# board-v2.net
KiCad netlist of a schematic drawn in EAGLE
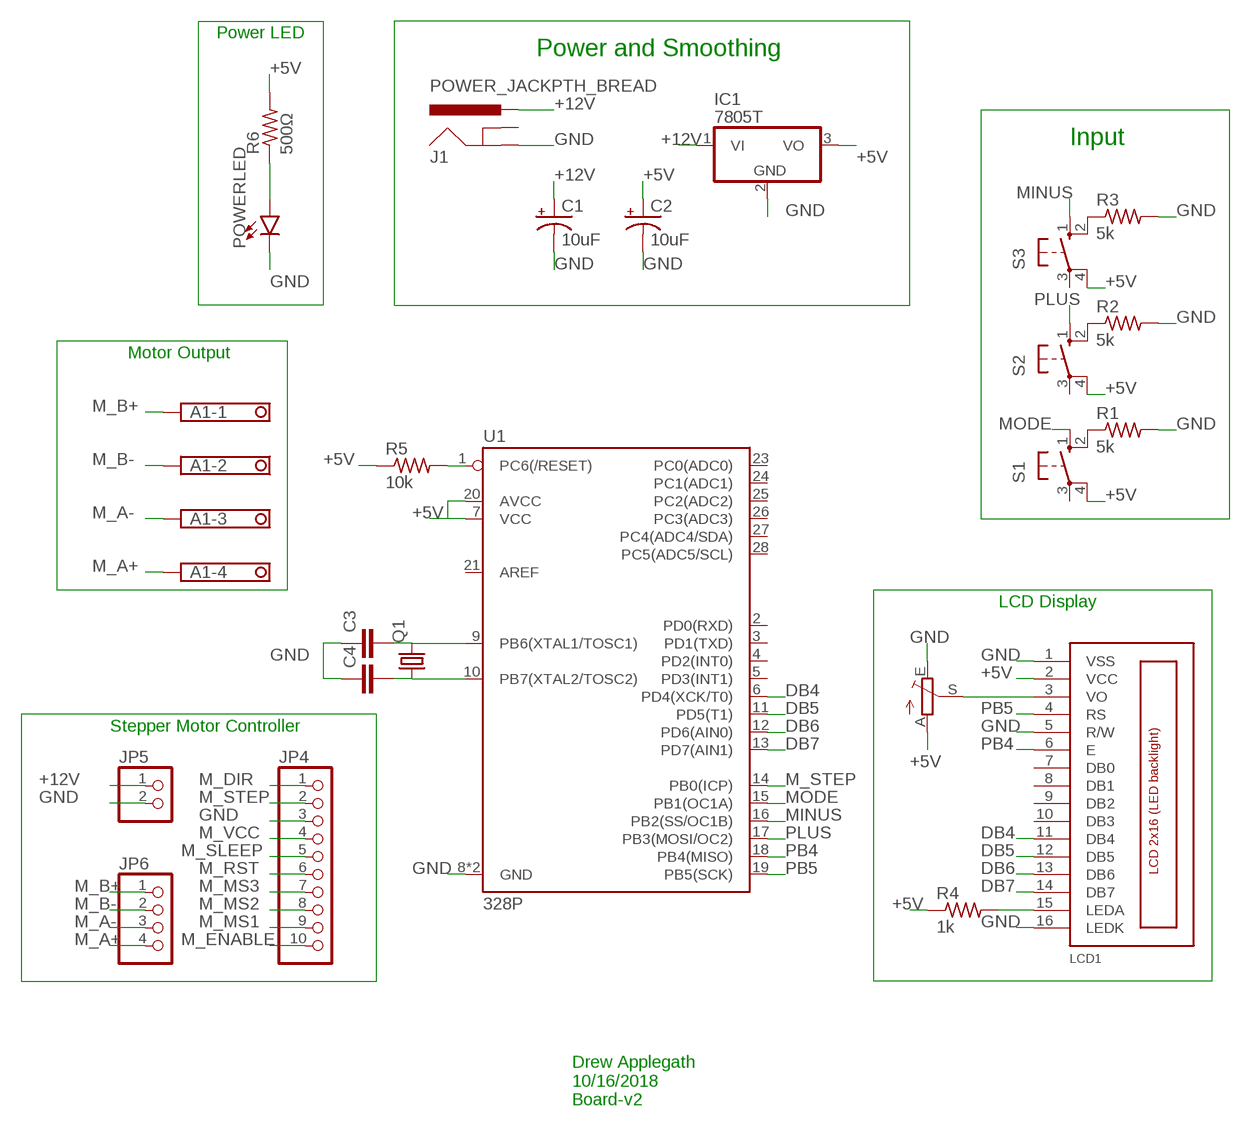
[diagram p0: schematic, sheet 1]

(export (version "E")
  (design (tool "Eeschema 10.0.6"))
  (components
    (comp (ref "A1")
      (value "TERMINAL-BLOCK-3.5MM-4-PIN-LONG-PAD")
      (footprint "eagle-import:TERMINAL-BLOCK-4-PIN-3.5MM-LONG-PAD")
      (libsource (lib "eagle-import") (part "TERMINAL-BLOCK-3.5MM-4-PIN-LONG-PAD"))
    )
    (comp (ref "C1")
      (value "10uF")
      (footprint "eagle-import:CPOL-RADIAL-2.5MM-5MM")
      (libsource (lib "eagle-import") (part "10UF-POLAR-RADIAL-2.5MM-25V-20%"))
    )
    (comp (ref "C2")
      (value "10uF")
      (footprint "eagle-import:CPOL-RADIAL-2.5MM-5MM")
      (libsource (lib "eagle-import") (part "10UF-POLAR-RADIAL-2.5MM-25V-20%"))
    )
    (comp (ref "C3")
      (value "C-EU025-024X044")
      (footprint "eagle-import:C025-024X044")
      (libsource (lib "eagle-import") (part "C-EU025-024X044"))
    )
    (comp (ref "C4")
      (value "C-EU025-024X044")
      (footprint "eagle-import:C025-024X044")
      (libsource (lib "eagle-import") (part "C-EU025-024X044"))
    )
    (comp (ref "IC1")
      (value "7805T")
      (footprint "eagle-import:TO220H")
      (libsource (lib "eagle-import") (part "78T05"))
    )
    (comp (ref "J1")
      (value "POWER_JACKPTH_BREAD")
      (footprint "eagle-import:POWER_JACK_PTH_BREAD")
      (libsource (lib "eagle-import") (part "POWER_JACKPTH_BREAD"))
    )
    (comp (ref "JP4")
      (value "PINHD-1X10")
      (footprint "eagle-import:1X10")
      (libsource (lib "eagle-import") (part "PINHD-1X10"))
    )
    (comp (ref "JP5")
      (value "PINHD-1X2")
      (footprint "eagle-import:1X02")
      (libsource (lib "eagle-import") (part "PINHD-1X2"))
    )
    (comp (ref "JP6")
      (value "PINHD-1X4")
      (footprint "eagle-import:1X04")
      (libsource (lib "eagle-import") (part "PINHD-1X4"))
    )
    (comp (ref "LCD1")
      (value "LCD_2X16_SIL")
      (footprint "eagle-import:HY-1602F")
      (libsource (lib "eagle-import") (part "LCD_2X16_SIL"))
    )
    (comp (ref "POWERLED")
      (value "LED-3MM-NO_SILK")
      (footprint "eagle-import:LED_3MM-NS")
      (libsource (lib "eagle-import") (part "LED-3MM-NO_SILK"))
    )
    (comp (ref "Q1")
      (value "CRYSTALHC49S")
      (footprint "eagle-import:HC49_S")
      (libsource (lib "eagle-import") (part "CRYSTALHC49S"))
    )
    (comp (ref "R1")
      (value "5k")
      (footprint "eagle-import:0207_7")
      (libsource (lib "eagle-import") (part "R-US_0207/7"))
    )
    (comp (ref "R2")
      (value "5k")
      (footprint "eagle-import:0207_7")
      (libsource (lib "eagle-import") (part "R-US_0207/7"))
    )
    (comp (ref "R3")
      (value "5k")
      (footprint "eagle-import:0207_7")
      (libsource (lib "eagle-import") (part "R-US_0207/7"))
    )
    (comp (ref "R4")
      (value "1k")
      (footprint "eagle-import:0207_7")
      (libsource (lib "eagle-import") (part "R-US_0207/7"))
    )
    (comp (ref "R5")
      (value "10k")
      (footprint "eagle-import:0207_7")
      (libsource (lib "eagle-import") (part "R-US_0207/7"))
    )
    (comp (ref "R6")
      (value "500Ω")
      (footprint "eagle-import:0207_7")
      (libsource (lib "eagle-import") (part "R-US_0207/7"))
    )
    (comp (ref "R7")
      (value "TRIM_EU-S63S")
      (footprint "eagle-import:S63S")
      (libsource (lib "eagle-import") (part "TRIM_EU-S63S"))
    )
    (comp (ref "S1")
      (value "40-XX")
      (footprint "eagle-import:B3F-40XX")
      (fields (field (name "MF") "OMRON COMPONENTS USA") (field (name "MPN") "B3F-4000"))
      (libsource (lib "eagle-import") (part "40-XX"))
    )
    (comp (ref "S2")
      (value "40-XX")
      (footprint "eagle-import:B3F-40XX")
      (fields (field (name "MF") "OMRON COMPONENTS USA") (field (name "MPN") "B3F-4000"))
      (libsource (lib "eagle-import") (part "40-XX"))
    )
    (comp (ref "S3")
      (value "40-XX")
      (footprint "eagle-import:B3F-40XX")
      (fields (field (name "MF") "OMRON COMPONENTS USA") (field (name "MPN") "B3F-4000"))
      (libsource (lib "eagle-import") (part "40-XX"))
    )
    (comp (ref "U1")
      (value "328P")
      (footprint "eagle-import:DIP28")
      (libsource (lib "eagle-import") (part "ATMEGA328P_PDIP"))
    )
  )
  (nets
    (net (code "1") (name "/+5V") (class "Default")
      (node (ref "C2") (pin "1") (pinfunction "+_1") (pintype "passive"))
      (node (ref "IC1") (pin "3") (pinfunction "VO_3") (pintype "passive"))
      (node (ref "LCD1") (pin "2") (pinfunction "VCC_2") (pintype "power_in"))
      (node (ref "R4") (pin "1") (pinfunction "1_1") (pintype "passive"))
      (node (ref "R5") (pin "1") (pinfunction "1_1") (pintype "passive"))
      (node (ref "R6") (pin "2") (pinfunction "2_2") (pintype "passive"))
      (node (ref "R7") (pin "A") (pinfunction "A_A") (pintype "passive"))
      (node (ref "S1") (pin "4") (pinfunction "P1_4") (pintype "passive"))
      (node (ref "S2") (pin "4") (pinfunction "P1_4") (pintype "passive"))
      (node (ref "S3") (pin "4") (pinfunction "P1_4") (pintype "passive"))
      (node (ref "U1") (pin "20") (pinfunction "AVCC_20") (pintype "bidirectional"))
      (node (ref "U1") (pin "7") (pinfunction "VCC_7") (pintype "bidirectional"))
    )
    (net (code "2") (name "/+12V") (class "Default")
      (node (ref "C1") (pin "1") (pinfunction "+_1") (pintype "passive"))
      (node (ref "IC1") (pin "1") (pinfunction "VI_1") (pintype "input"))
      (node (ref "J1") (pin "PWR") (pinfunction "PWR_PWR") (pintype "bidirectional"))
      (node (ref "JP5") (pin "1") (pinfunction "1_1") (pintype "passive"))
    )
    (net (code "3") (name "/DB4") (class "Default")
      (node (ref "LCD1") (pin "11") (pinfunction "DB4_11") (pintype "bidirectional"))
      (node (ref "U1") (pin "6") (pinfunction "PD4(XCK/T0)_6") (pintype "bidirectional"))
    )
    (net (code "4") (name "/DB5") (class "Default")
      (node (ref "LCD1") (pin "12") (pinfunction "DB5_12") (pintype "bidirectional"))
      (node (ref "U1") (pin "11") (pinfunction "PD5(T1)_11") (pintype "bidirectional"))
    )
    (net (code "5") (name "/DB6") (class "Default")
      (node (ref "LCD1") (pin "13") (pinfunction "DB6_13") (pintype "bidirectional"))
      (node (ref "U1") (pin "12") (pinfunction "PD6(AIN0)_12") (pintype "bidirectional"))
    )
    (net (code "6") (name "/DB7") (class "Default")
      (node (ref "LCD1") (pin "14") (pinfunction "DB7_14") (pintype "bidirectional"))
      (node (ref "U1") (pin "13") (pinfunction "PD7(AIN1)_13") (pintype "bidirectional"))
    )
    (net (code "7") (name "/GND") (class "Default")
      (node (ref "C1") (pin "2") (pinfunction "-_2") (pintype "passive"))
      (node (ref "C2") (pin "2") (pinfunction "-_2") (pintype "passive"))
      (node (ref "C3") (pin "1") (pinfunction "1_1") (pintype "passive"))
      (node (ref "C4") (pin "1") (pinfunction "1_1") (pintype "passive"))
      (node (ref "IC1") (pin "2") (pinfunction "GND_2") (pintype "passive"))
      (node (ref "J1") (pin "GND") (pinfunction "GND_GND") (pintype "bidirectional"))
      (node (ref "JP4") (pin "3") (pinfunction "3_3") (pintype "passive"))
      (node (ref "JP5") (pin "2") (pinfunction "2_2") (pintype "passive"))
      (node (ref "LCD1") (pin "1") (pinfunction "VSS_1") (pintype "power_in"))
      (node (ref "LCD1") (pin "16") (pinfunction "LEDK_16") (pintype "passive"))
      (node (ref "LCD1") (pin "5") (pinfunction "R/W_5") (pintype "input"))
      (node (ref "POWERLED") (pin "K") (pinfunction "C_K") (pintype "passive"))
      (node (ref "R1") (pin "2") (pinfunction "2_2") (pintype "passive"))
      (node (ref "R2") (pin "2") (pinfunction "2_2") (pintype "passive"))
      (node (ref "R3") (pin "2") (pinfunction "2_2") (pintype "passive"))
      (node (ref "R7") (pin "E") (pinfunction "E_E") (pintype "passive"))
      (node (ref "U1") (pin "22") (pinfunction "GND_22") (pintype "bidirectional"))
      (node (ref "U1") (pin "8") (pinfunction "GND_8") (pintype "bidirectional"))
    )
    (net (code "8") (name "/MINUS") (class "Default")
      (node (ref "S3") (pin "1") (pinfunction "S_1") (pintype "passive"))
      (node (ref "U1") (pin "16") (pinfunction "PB2(SS/OC1B)_16") (pintype "bidirectional"))
    )
    (net (code "9") (name "/MODE") (class "Default")
      (node (ref "S1") (pin "1") (pinfunction "S_1") (pintype "passive"))
      (node (ref "U1") (pin "15") (pinfunction "PB1(OC1A)_15") (pintype "bidirectional"))
    )
    (net (code "10") (name "/M_A+") (class "Default")
      (node (ref "A1") (pin "4") (pinfunction "K_4") (pintype "passive"))
      (node (ref "JP6") (pin "4") (pinfunction "4_4") (pintype "passive"))
    )
    (net (code "11") (name "/M_A-") (class "Default")
      (node (ref "A1") (pin "3") (pinfunction "K_3") (pintype "passive"))
      (node (ref "JP6") (pin "3") (pinfunction "3_3") (pintype "passive"))
    )
    (net (code "12") (name "/M_B+") (class "Default")
      (node (ref "A1") (pin "1") (pinfunction "K_1") (pintype "passive"))
      (node (ref "JP6") (pin "1") (pinfunction "1_1") (pintype "passive"))
    )
    (net (code "13") (name "/M_B-") (class "Default")
      (node (ref "A1") (pin "2") (pinfunction "K_2") (pintype "passive"))
      (node (ref "JP6") (pin "2") (pinfunction "2_2") (pintype "passive"))
    )
    (net (code "14") (name "/M_DIR") (class "Default")
      (node (ref "JP4") (pin "1") (pinfunction "1_1") (pintype "passive"))
    )
    (net (code "15") (name "/M_ENABLE") (class "Default")
      (node (ref "JP4") (pin "10") (pinfunction "10_10") (pintype "passive"))
    )
    (net (code "16") (name "/M_MS1") (class "Default")
      (node (ref "JP4") (pin "9") (pinfunction "9_9") (pintype "passive"))
    )
    (net (code "17") (name "/M_MS2") (class "Default")
      (node (ref "JP4") (pin "8") (pinfunction "8_8") (pintype "passive"))
    )
    (net (code "18") (name "/M_MS3") (class "Default")
      (node (ref "JP4") (pin "7") (pinfunction "7_7") (pintype "passive"))
    )
    (net (code "19") (name "/M_RST") (class "Default")
      (node (ref "JP4") (pin "6") (pinfunction "6_6") (pintype "passive"))
    )
    (net (code "20") (name "/M_SLEEP") (class "Default")
      (node (ref "JP4") (pin "5") (pinfunction "5_5") (pintype "passive"))
    )
    (net (code "21") (name "/M_STEP") (class "Default")
      (node (ref "JP4") (pin "2") (pinfunction "2_2") (pintype "passive"))
      (node (ref "U1") (pin "14") (pinfunction "PB0(ICP)_14") (pintype "bidirectional"))
    )
    (net (code "22") (name "/M_VCC") (class "Default")
      (node (ref "JP4") (pin "4") (pinfunction "4_4") (pintype "passive"))
    )
    (net (code "23") (name "/PB4") (class "Default")
      (node (ref "LCD1") (pin "6") (pinfunction "E_6") (pintype "input"))
      (node (ref "U1") (pin "18") (pinfunction "PB4(MISO)_18") (pintype "bidirectional"))
    )
    (net (code "24") (name "/PB5") (class "Default")
      (node (ref "LCD1") (pin "4") (pinfunction "RS_4") (pintype "input"))
      (node (ref "U1") (pin "19") (pinfunction "PB5(SCK)_19") (pintype "bidirectional"))
    )
    (net (code "25") (name "/PLUS") (class "Default")
      (node (ref "S2") (pin "1") (pinfunction "S_1") (pintype "passive"))
      (node (ref "U1") (pin "17") (pinfunction "PB3(MOSI/OC2)_17") (pintype "bidirectional"))
    )
    (net (code "26") (name "Net-(LCD1-LEDA)") (class "Default")
      (node (ref "LCD1") (pin "15") (pinfunction "LEDA_15") (pintype "passive"))
      (node (ref "R4") (pin "2") (pinfunction "2_2") (pintype "passive"))
    )
    (net (code "27") (name "Net-(LCD1-VO)") (class "Default")
      (node (ref "LCD1") (pin "3") (pinfunction "VO_3") (pintype "input"))
      (node (ref "R7") (pin "S") (pinfunction "S_S") (pintype "passive"))
    )
    (net (code "28") (name "Net-(POWERLED-PadA)") (class "Default")
      (node (ref "POWERLED") (pin "A") (pinfunction "A_A") (pintype "passive"))
      (node (ref "R6") (pin "1") (pinfunction "1_1") (pintype "passive"))
    )
    (net (code "29") (name "Net-(S1-S1)") (class "Default")
      (node (ref "R1") (pin "1") (pinfunction "1_1") (pintype "passive"))
      (node (ref "S1") (pin "2") (pinfunction "S1_2") (pintype "passive"))
    )
    (net (code "30") (name "Net-(S2-S1)") (class "Default")
      (node (ref "R2") (pin "1") (pinfunction "1_1") (pintype "passive"))
      (node (ref "S2") (pin "2") (pinfunction "S1_2") (pintype "passive"))
    )
    (net (code "31") (name "Net-(S3-S1)") (class "Default")
      (node (ref "R3") (pin "1") (pinfunction "1_1") (pintype "passive"))
      (node (ref "S3") (pin "2") (pinfunction "S1_2") (pintype "passive"))
    )
    (net (code "32") (name "Net-(U1-PB6(XTAL1{slash}TOSC1))") (class "Default")
      (node (ref "C3") (pin "2") (pinfunction "2_2") (pintype "passive"))
      (node (ref "Q1") (pin "2") (pinfunction "2_2") (pintype "passive"))
      (node (ref "U1") (pin "9") (pinfunction "PB6(XTAL1/TOSC1)_9") (pintype "bidirectional"))
    )
    (net (code "33") (name "Net-(U1-PB7(XTAL2{slash}TOSC2))") (class "Default")
      (node (ref "C4") (pin "2") (pinfunction "2_2") (pintype "passive"))
      (node (ref "Q1") (pin "1") (pinfunction "1_1") (pintype "passive"))
      (node (ref "U1") (pin "10") (pinfunction "PB7(XTAL2/TOSC2)_10") (pintype "bidirectional"))
    )
    (net (code "34") (name "Net-(U1-PC6({slash}RESET))") (class "Default")
      (node (ref "R5") (pin "2") (pinfunction "2_2") (pintype "passive"))
      (node (ref "U1") (pin "1") (pinfunction "PC6(/RESET)_1") (pintype "bidirectional"))
    )
    (net (code "35") (name "unconnected-(J1-PadGNDBREAK)") (class "Default")
      (node (ref "J1") (pin "GNDBREAK") (pinfunction "GNDBREAK_GNDBREAK") (pintype "bidirectional"))
    )
    (net (code "36") (name "unconnected-(LCD1-DB0-Pad7)") (class "Default")
      (node (ref "LCD1") (pin "7") (pinfunction "DB0_7") (pintype "bidirectional"))
    )
    (net (code "37") (name "unconnected-(LCD1-DB1-Pad8)") (class "Default")
      (node (ref "LCD1") (pin "8") (pinfunction "DB1_8") (pintype "bidirectional"))
    )
    (net (code "38") (name "unconnected-(LCD1-DB2-Pad9)") (class "Default")
      (node (ref "LCD1") (pin "9") (pinfunction "DB2_9") (pintype "bidirectional"))
    )
    (net (code "39") (name "unconnected-(LCD1-DB3-Pad10)") (class "Default")
      (node (ref "LCD1") (pin "10") (pinfunction "DB3_10") (pintype "bidirectional"))
    )
    (net (code "40") (name "unconnected-(S1-P-Pad3)") (class "Default")
      (node (ref "S1") (pin "3") (pinfunction "P_3") (pintype "passive"))
    )
    (net (code "41") (name "unconnected-(S2-P-Pad3)") (class "Default")
      (node (ref "S2") (pin "3") (pinfunction "P_3") (pintype "passive"))
    )
    (net (code "42") (name "unconnected-(S3-P-Pad3)") (class "Default")
      (node (ref "S3") (pin "3") (pinfunction "P_3") (pintype "passive"))
    )
    (net (code "43") (name "unconnected-(U1-AREF-Pad21)") (class "Default")
      (node (ref "U1") (pin "21") (pinfunction "AREF_21") (pintype "bidirectional"))
    )
    (net (code "44") (name "unconnected-(U1-PC0(ADC0)-Pad23)") (class "Default")
      (node (ref "U1") (pin "23") (pinfunction "PC0(ADC0)_23") (pintype "bidirectional"))
    )
    (net (code "45") (name "unconnected-(U1-PC1(ADC1)-Pad24)") (class "Default")
      (node (ref "U1") (pin "24") (pinfunction "PC1(ADC1)_24") (pintype "bidirectional"))
    )
    (net (code "46") (name "unconnected-(U1-PC2(ADC2)-Pad25)") (class "Default")
      (node (ref "U1") (pin "25") (pinfunction "PC2(ADC2)_25") (pintype "bidirectional"))
    )
    (net (code "47") (name "unconnected-(U1-PC3(ADC3)-Pad26)") (class "Default")
      (node (ref "U1") (pin "26") (pinfunction "PC3(ADC3)_26") (pintype "bidirectional"))
    )
    (net (code "48") (name "unconnected-(U1-PC4(ADC4{slash}SDA)-Pad27)") (class "Default")
      (node (ref "U1") (pin "27") (pinfunction "PC4(ADC4/SDA)_27") (pintype "bidirectional"))
    )
    (net (code "49") (name "unconnected-(U1-PC5(ADC5{slash}SCL)-Pad28)") (class "Default")
      (node (ref "U1") (pin "28") (pinfunction "PC5(ADC5/SCL)_28") (pintype "bidirectional"))
    )
    (net (code "50") (name "unconnected-(U1-PD0(RXD)-Pad2)") (class "Default")
      (node (ref "U1") (pin "2") (pinfunction "PD0(RXD)_2") (pintype "bidirectional"))
    )
    (net (code "51") (name "unconnected-(U1-PD1(TXD)-Pad3)") (class "Default")
      (node (ref "U1") (pin "3") (pinfunction "PD1(TXD)_3") (pintype "bidirectional"))
    )
    (net (code "52") (name "unconnected-(U1-PD2(INT0)-Pad4)") (class "Default")
      (node (ref "U1") (pin "4") (pinfunction "PD2(INT0)_4") (pintype "bidirectional"))
    )
    (net (code "53") (name "unconnected-(U1-PD3(INT1)-Pad5)") (class "Default")
      (node (ref "U1") (pin "5") (pinfunction "PD3(INT1)_5") (pintype "bidirectional"))
    )
  )
)
